# Adafruit_STMPE610.net
KiCad netlist of a schematic drawn in EAGLE
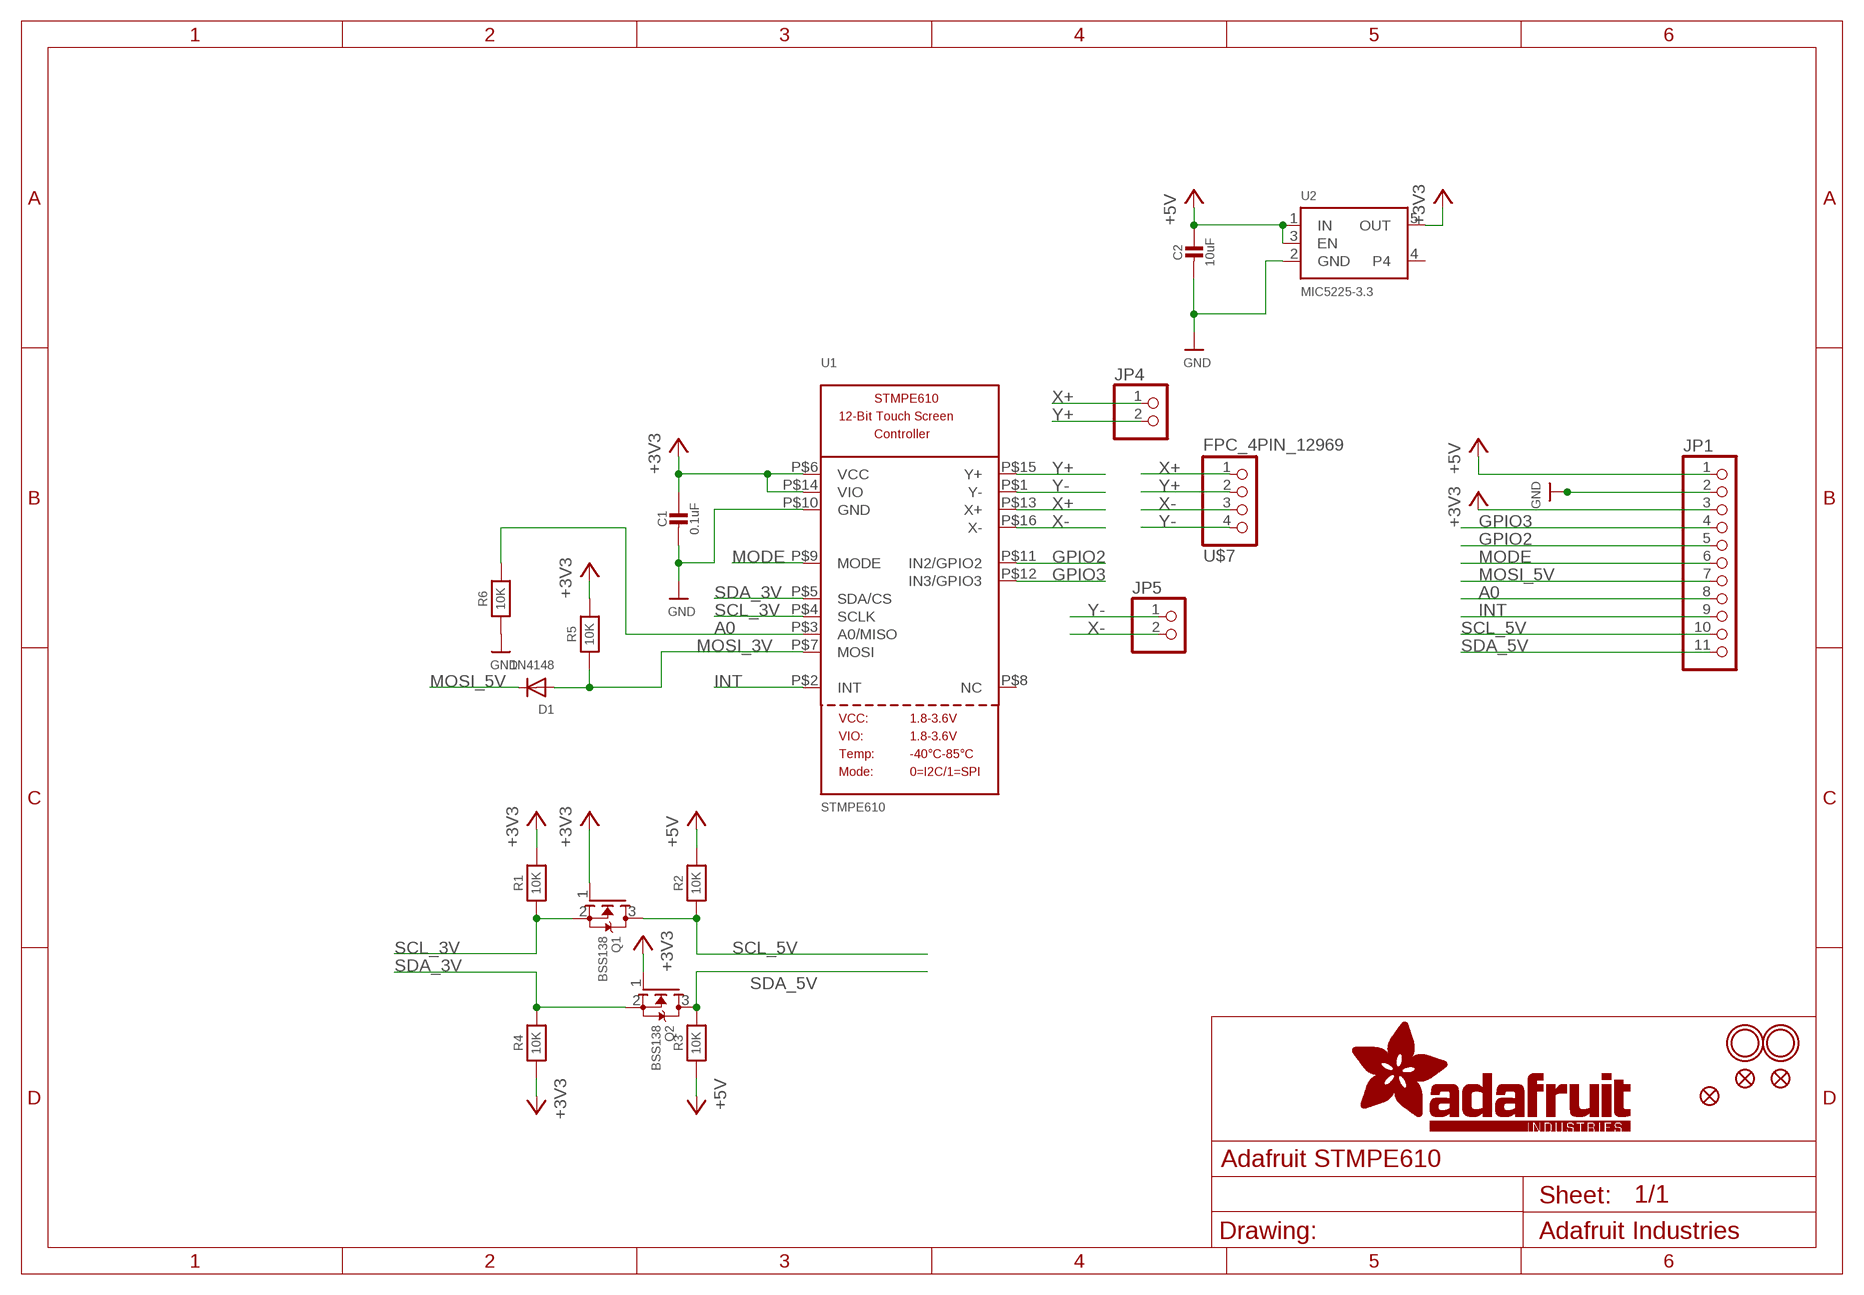
[diagram p0: schematic, sheet 1]

(export (version "E")
  (design (tool "Eeschema 10.0.6"))
  (components
    (comp (ref "C1")
      (value "0.1uF")
      (footprint "eagle-import:0805-NO")
      (libsource (lib "eagle-import") (part "CAP_CERAMIC0805-NOOUTLINE"))
    )
    (comp (ref "C2")
      (value "10uF")
      (footprint "eagle-import:0805-NO")
      (libsource (lib "eagle-import") (part "CAP_CERAMIC0805-NOOUTLINE"))
    )
    (comp (ref "D1")
      (value "1N4148")
      (footprint "eagle-import:SOD-323F")
      (libsource (lib "eagle-import") (part "DIODESOD-323F"))
    )
    (comp (ref "FID1")
      (value "FIDUCIAL\"\"")
      (footprint "eagle-import:FIDUCIAL_1MM")
      (libsource (lib "eagle-import") (part "FIDUCIAL{dblquote}{dblquote}"))
    )
    (comp (ref "FID2")
      (value "FIDUCIAL\"\"")
      (footprint "eagle-import:FIDUCIAL_1MM")
      (libsource (lib "eagle-import") (part "FIDUCIAL{dblquote}{dblquote}"))
    )
    (comp (ref "FID3")
      (value "FIDUCIAL\"\"")
      (footprint "eagle-import:FIDUCIAL_1MM")
      (fields (field (name "BOM") "EXCLUDE"))
      (libsource (lib "eagle-import") (part "FIDUCIAL{dblquote}{dblquote}"))
    )
    (comp (ref "JP1")
      (value "HEADER-1X11")
      (footprint "eagle-import:1X11_ROUND")
      (libsource (lib "eagle-import") (part "HEADER-1X11"))
    )
    (comp (ref "JP4")
      (value "HEADER-1X2ROUND")
      (footprint "eagle-import:1X02_ROUND")
      (libsource (lib "eagle-import") (part "HEADER-1X2ROUND"))
    )
    (comp (ref "JP5")
      (value "HEADER-1X2ROUND")
      (footprint "eagle-import:1X02_ROUND")
      (libsource (lib "eagle-import") (part "HEADER-1X2ROUND"))
    )
    (comp (ref "Q1")
      (value "BSS138")
      (footprint "eagle-import:SOT23")
      (libsource (lib "eagle-import") (part "MOSFET-NREFLOW"))
    )
    (comp (ref "Q2")
      (value "BSS138")
      (footprint "eagle-import:SOT23")
      (libsource (lib "eagle-import") (part "MOSFET-NREFLOW"))
    )
    (comp (ref "R1")
      (value "10K")
      (footprint "eagle-import:0805-NO")
      (libsource (lib "eagle-import") (part "RESISTOR0805_NOOUTLINE"))
    )
    (comp (ref "R2")
      (value "10K")
      (footprint "eagle-import:0805-NO")
      (libsource (lib "eagle-import") (part "RESISTOR0805_NOOUTLINE"))
    )
    (comp (ref "R3")
      (value "10K")
      (footprint "eagle-import:0805-NO")
      (libsource (lib "eagle-import") (part "RESISTOR0805_NOOUTLINE"))
    )
    (comp (ref "R4")
      (value "10K")
      (footprint "eagle-import:0805-NO")
      (libsource (lib "eagle-import") (part "RESISTOR0805_NOOUTLINE"))
    )
    (comp (ref "R5")
      (value "10K")
      (footprint "eagle-import:0805-NO")
      (libsource (lib "eagle-import") (part "RESISTOR0805_NOOUTLINE"))
    )
    (comp (ref "R6")
      (value "10K")
      (footprint "eagle-import:0805-NO")
      (libsource (lib "eagle-import") (part "RESISTOR0805_NOOUTLINE"))
    )
    (comp (ref "U$4")
      (value "MOUNTINGHOLE2.5")
      (footprint "eagle-import:MOUNTINGHOLE_2.5_PLATED")
      (libsource (lib "eagle-import") (part "MOUNTINGHOLE2.5"))
    )
    (comp (ref "U$5")
      (value "MOUNTINGHOLE2.5")
      (footprint "eagle-import:MOUNTINGHOLE_2.5_PLATED")
      (libsource (lib "eagle-import") (part "MOUNTINGHOLE2.5"))
    )
    (comp (ref "U$7")
      (value "FPC_4PIN_12969")
      (footprint "eagle-import:FPC_CONN_1MM_DUAL_4P")
      (libsource (lib "eagle-import") (part "FPC_4PIN_12969"))
    )
    (comp (ref "U1")
      (value "STMPE610")
      (footprint "eagle-import:QFN16_3MM")
      (libsource (lib "eagle-import") (part "STMPE610"))
    )
    (comp (ref "U2")
      (value "MIC5225-3.3")
      (footprint "eagle-import:SOT23-5")
      (libsource (lib "eagle-import") (part "VREG_SOT23-5"))
    )
  )
  (nets
    (net (code "1") (name "+3V3") (class "Default")
      (node (ref "C1") (pin "1") (pinfunction "1_1") (pintype "passive"))
      (node (ref "JP1") (pin "3") (pinfunction "3_3") (pintype "passive"))
      (node (ref "Q1") (pin "1") (pinfunction "G_1") (pintype "bidirectional"))
      (node (ref "Q2") (pin "1") (pinfunction "G_1") (pintype "bidirectional"))
      (node (ref "R1") (pin "2") (pinfunction "2_2") (pintype "passive"))
      (node (ref "R4") (pin "1") (pinfunction "1_1") (pintype "passive"))
      (node (ref "R5") (pin "2") (pinfunction "2_2") (pintype "passive"))
      (node (ref "U1") (pin "P$14") (pinfunction "VIO_P$14") (pintype "power_in"))
      (node (ref "U1") (pin "P$6") (pinfunction "VCC_P$6") (pintype "power_in"))
      (node (ref "U2") (pin "5") (pinfunction "OUT_5") (pintype "power_in"))
    )
    (net (code "2") (name "+5V") (class "Default")
      (node (ref "C2") (pin "1") (pinfunction "1_1") (pintype "passive"))
      (node (ref "JP1") (pin "1") (pinfunction "1_1") (pintype "passive"))
      (node (ref "R2") (pin "2") (pinfunction "2_2") (pintype "passive"))
      (node (ref "R3") (pin "1") (pinfunction "1_1") (pintype "passive"))
      (node (ref "U2") (pin "1") (pinfunction "IN_1") (pintype "power_in"))
      (node (ref "U2") (pin "3") (pinfunction "EN_3") (pintype "input"))
    )
    (net (code "3") (name "/A0") (class "Default")
      (node (ref "JP1") (pin "8") (pinfunction "8_8") (pintype "passive"))
      (node (ref "R6") (pin "2") (pinfunction "2_2") (pintype "passive"))
      (node (ref "U1") (pin "P$3") (pinfunction "A0/MISO_P$3") (pintype "bidirectional"))
    )
    (net (code "4") (name "/GPIO2") (class "Default")
      (node (ref "JP1") (pin "5") (pinfunction "5_5") (pintype "passive"))
      (node (ref "U1") (pin "P$11") (pinfunction "IN2/GPIO2_P$11") (pintype "bidirectional"))
    )
    (net (code "5") (name "/GPIO3") (class "Default")
      (node (ref "JP1") (pin "4") (pinfunction "4_4") (pintype "passive"))
      (node (ref "U1") (pin "P$12") (pinfunction "IN3/GPIO3_P$12") (pintype "bidirectional"))
    )
    (net (code "6") (name "/INT") (class "Default")
      (node (ref "JP1") (pin "9") (pinfunction "9_9") (pintype "passive"))
      (node (ref "U1") (pin "P$2") (pinfunction "INT_P$2") (pintype "output"))
    )
    (net (code "7") (name "/MODE") (class "Default")
      (node (ref "JP1") (pin "6") (pinfunction "6_6") (pintype "passive"))
      (node (ref "U1") (pin "P$9") (pinfunction "MODE_P$9") (pintype "input"))
    )
    (net (code "8") (name "/MOSI_3V") (class "Default")
      (node (ref "D1") (pin "A") (pinfunction "A_A") (pintype "passive"))
      (node (ref "R5") (pin "1") (pinfunction "1_1") (pintype "passive"))
      (node (ref "U1") (pin "P$7") (pinfunction "MOSI_P$7") (pintype "input"))
    )
    (net (code "9") (name "/MOSI_5V") (class "Default")
      (node (ref "D1") (pin "C") (pinfunction "C_C") (pintype "passive"))
      (node (ref "JP1") (pin "7") (pinfunction "7_7") (pintype "passive"))
    )
    (net (code "10") (name "/SCL_3V") (class "Default")
      (node (ref "Q1") (pin "2") (pinfunction "S_2") (pintype "bidirectional"))
      (node (ref "R1") (pin "1") (pinfunction "1_1") (pintype "passive"))
      (node (ref "U1") (pin "P$4") (pinfunction "SCLK_P$4") (pintype "bidirectional"))
    )
    (net (code "11") (name "/SCL_5V") (class "Default")
      (node (ref "JP1") (pin "10") (pinfunction "10_10") (pintype "passive"))
      (node (ref "Q1") (pin "3") (pinfunction "D_3") (pintype "bidirectional"))
      (node (ref "R2") (pin "1") (pinfunction "1_1") (pintype "passive"))
    )
    (net (code "12") (name "/SDA_3V") (class "Default")
      (node (ref "Q2") (pin "2") (pinfunction "S_2") (pintype "bidirectional"))
      (node (ref "R4") (pin "2") (pinfunction "2_2") (pintype "passive"))
      (node (ref "U1") (pin "P$5") (pinfunction "SDA/CS_P$5") (pintype "bidirectional"))
    )
    (net (code "13") (name "/SDA_5V") (class "Default")
      (node (ref "JP1") (pin "11") (pinfunction "11_11") (pintype "passive"))
      (node (ref "Q2") (pin "3") (pinfunction "D_3") (pintype "bidirectional"))
      (node (ref "R3") (pin "2") (pinfunction "2_2") (pintype "passive"))
    )
    (net (code "14") (name "/X+") (class "Default")
      (node (ref "JP4") (pin "1") (pinfunction "1_1") (pintype "passive"))
      (node (ref "U$7") (pin "1") (pinfunction "4_1") (pintype "passive"))
      (node (ref "U1") (pin "P$13") (pinfunction "X+_P$13") (pintype "input"))
    )
    (net (code "15") (name "/X-") (class "Default")
      (node (ref "JP5") (pin "2") (pinfunction "2_2") (pintype "passive"))
      (node (ref "U$7") (pin "3") (pinfunction "2_3") (pintype "passive"))
      (node (ref "U1") (pin "P$16") (pinfunction "X-_P$16") (pintype "input"))
    )
    (net (code "16") (name "/Y+") (class "Default")
      (node (ref "JP4") (pin "2") (pinfunction "2_2") (pintype "passive"))
      (node (ref "U$7") (pin "2") (pinfunction "3_2") (pintype "passive"))
      (node (ref "U1") (pin "P$15") (pinfunction "Y+_P$15") (pintype "input"))
    )
    (net (code "17") (name "/Y-") (class "Default")
      (node (ref "JP5") (pin "1") (pinfunction "1_1") (pintype "passive"))
      (node (ref "U$7") (pin "4") (pinfunction "1_4") (pintype "passive"))
      (node (ref "U1") (pin "P$1") (pinfunction "Y-_P$1") (pintype "input"))
    )
    (net (code "18") (name "GND") (class "Default")
      (node (ref "C1") (pin "2") (pinfunction "2_2") (pintype "passive"))
      (node (ref "C2") (pin "2") (pinfunction "2_2") (pintype "passive"))
      (node (ref "JP1") (pin "2") (pinfunction "2_2") (pintype "passive"))
      (node (ref "R6") (pin "1") (pinfunction "1_1") (pintype "passive"))
      (node (ref "U1") (pin "P$10") (pinfunction "GND_P$10") (pintype "power_in"))
      (node (ref "U2") (pin "2") (pinfunction "GND_2") (pintype "power_in"))
    )
    (net (code "19") (name "unconnected-(U1-NC-PadP$8)") (class "Default")
      (node (ref "U1") (pin "P$8") (pinfunction "NC_P$8") (pintype "no_connect"))
    )
    (net (code "20") (name "unconnected-(U2-P4-Pad4)") (class "Default")
      (node (ref "U2") (pin "4") (pinfunction "P4_4") (pintype "bidirectional"))
    )
  )
)
